# Rev1_7.net
KiCad netlist of a schematic drawn in EAGLE
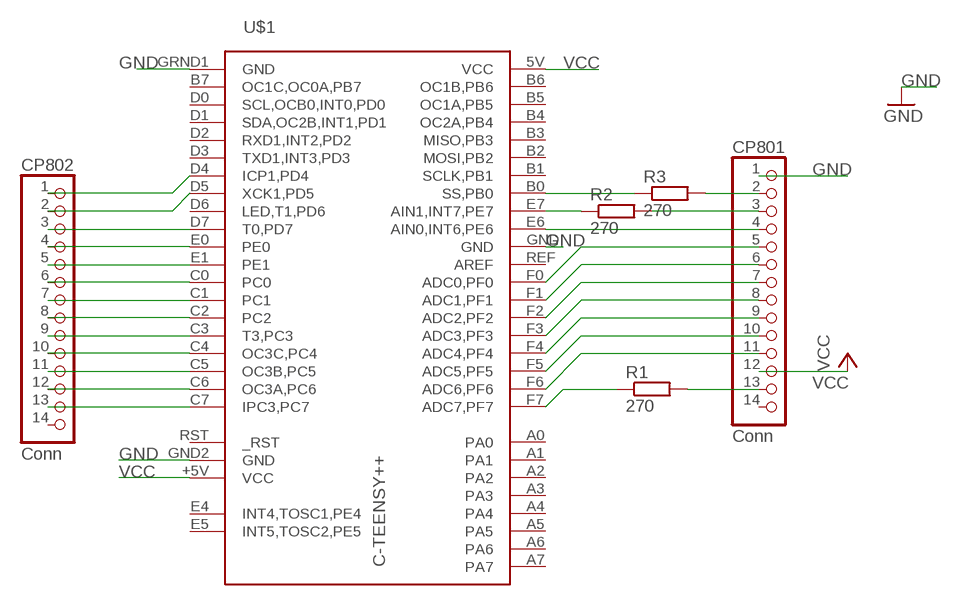
[diagram p0: schematic, sheet 1]

(export (version "E")
  (design (tool "Eeschema 10.0.6"))
  (components
    (comp (ref "CP801")
      (value "Conn")
      (footprint "eagle-import:1X14")
      (libsource (lib "eagle-import") (part "PINHD-1X14"))
    )
    (comp (ref "CP802")
      (value "Conn")
      (footprint "eagle-import:1X14")
      (libsource (lib "eagle-import") (part "PINHD-1X14"))
    )
    (comp (ref "R1")
      (value "270")
      (footprint "eagle-import:R0805")
      (libsource (lib "eagle-import") (part "R-EU_R0805"))
    )
    (comp (ref "R2")
      (value "270")
      (footprint "eagle-import:R0805")
      (libsource (lib "eagle-import") (part "R-EU_R0805"))
    )
    (comp (ref "R3")
      (value "270")
      (footprint "eagle-import:R0805")
      (libsource (lib "eagle-import") (part "R-EU_R0805"))
    )
    (comp (ref "U$1")
      (value "C-TEENSY++")
      (footprint "eagle-import:TEENSY++")
      (libsource (lib "eagle-import") (part "C-TEENSY++"))
    )
  )
  (nets
    (net (code "1") (name "GND") (class "Default")
      (node (ref "CP801") (pin "1") (pinfunction "1_1") (pintype "passive"))
      (node (ref "U$1") (pin "GND") (pinfunction "GND_GND") (pintype "power_in"))
      (node (ref "U$1") (pin "GND2") (pinfunction "GND_GND2") (pintype "power_in"))
      (node (ref "U$1") (pin "GRND1") (pinfunction "GND_GRND1") (pintype "power_in"))
    )
    (net (code "2") (name "Net-(CP801-Pad2)") (class "Default")
      (node (ref "CP801") (pin "2") (pinfunction "2_2") (pintype "passive"))
      (node (ref "R3") (pin "2") (pinfunction "2_2") (pintype "passive"))
    )
    (net (code "3") (name "Net-(CP801-Pad3)") (class "Default")
      (node (ref "CP801") (pin "3") (pinfunction "3_3") (pintype "passive"))
      (node (ref "R2") (pin "2") (pinfunction "2_2") (pintype "passive"))
    )
    (net (code "4") (name "Net-(CP801-Pad13)") (class "Default")
      (node (ref "CP801") (pin "13") (pinfunction "13_13") (pintype "passive"))
      (node (ref "R1") (pin "2") (pinfunction "2_2") (pintype "passive"))
    )
    (net (code "5") (name "Net-(U$1-ADC0,PF0)") (class "Default")
      (node (ref "CP801") (pin "5") (pinfunction "5_5") (pintype "passive"))
      (node (ref "U$1") (pin "F0") (pinfunction "ADC0,PF0_F0") (pintype "bidirectional"))
    )
    (net (code "6") (name "Net-(U$1-ADC1,PF1)") (class "Default")
      (node (ref "CP801") (pin "6") (pinfunction "6_6") (pintype "passive"))
      (node (ref "U$1") (pin "F1") (pinfunction "ADC1,PF1_F1") (pintype "bidirectional"))
    )
    (net (code "7") (name "Net-(U$1-ADC2,PF2)") (class "Default")
      (node (ref "CP801") (pin "7") (pinfunction "7_7") (pintype "passive"))
      (node (ref "U$1") (pin "F2") (pinfunction "ADC2,PF2_F2") (pintype "bidirectional"))
    )
    (net (code "8") (name "Net-(U$1-ADC3,PF3)") (class "Default")
      (node (ref "CP801") (pin "8") (pinfunction "8_8") (pintype "passive"))
      (node (ref "U$1") (pin "F3") (pinfunction "ADC3,PF3_F3") (pintype "bidirectional"))
    )
    (net (code "9") (name "Net-(U$1-ADC4,PF4)") (class "Default")
      (node (ref "CP801") (pin "9") (pinfunction "9_9") (pintype "passive"))
      (node (ref "U$1") (pin "F4") (pinfunction "ADC4,PF4_F4") (pintype "bidirectional"))
    )
    (net (code "10") (name "Net-(U$1-ADC5,PF5)") (class "Default")
      (node (ref "CP801") (pin "10") (pinfunction "10_10") (pintype "passive"))
      (node (ref "U$1") (pin "F5") (pinfunction "ADC5,PF5_F5") (pintype "bidirectional"))
    )
    (net (code "11") (name "Net-(U$1-ADC6,PF6)") (class "Default")
      (node (ref "CP801") (pin "11") (pinfunction "11_11") (pintype "passive"))
      (node (ref "U$1") (pin "F6") (pinfunction "ADC6,PF6_F6") (pintype "bidirectional"))
    )
    (net (code "12") (name "Net-(U$1-ADC7,PF7)") (class "Default")
      (node (ref "R1") (pin "1") (pinfunction "1_1") (pintype "passive"))
      (node (ref "U$1") (pin "F7") (pinfunction "ADC7,PF7_F7") (pintype "bidirectional"))
    )
    (net (code "13") (name "Net-(U$1-AIN0,INT6,PE6)") (class "Default")
      (node (ref "CP801") (pin "4") (pinfunction "4_4") (pintype "passive"))
      (node (ref "U$1") (pin "E6") (pinfunction "AIN0,INT6,PE6_E6") (pintype "bidirectional"))
    )
    (net (code "14") (name "Net-(U$1-AIN1,INT7,PE7)") (class "Default")
      (node (ref "R2") (pin "1") (pinfunction "1_1") (pintype "passive"))
      (node (ref "U$1") (pin "E7") (pinfunction "AIN1,INT7,PE7_E7") (pintype "bidirectional"))
    )
    (net (code "15") (name "Net-(U$1-ICP1,PD4)") (class "Default")
      (node (ref "CP802") (pin "1") (pinfunction "1_1") (pintype "passive"))
      (node (ref "U$1") (pin "D4") (pinfunction "ICP1,PD4_D4") (pintype "bidirectional"))
    )
    (net (code "16") (name "Net-(U$1-IPC3,PC7)") (class "Default")
      (node (ref "CP802") (pin "13") (pinfunction "13_13") (pintype "passive"))
      (node (ref "U$1") (pin "C7") (pinfunction "IPC3,PC7_C7") (pintype "bidirectional"))
    )
    (net (code "17") (name "Net-(U$1-OC3A,PC6)") (class "Default")
      (node (ref "CP802") (pin "12") (pinfunction "12_12") (pintype "passive"))
      (node (ref "U$1") (pin "C6") (pinfunction "OC3A,PC6_C6") (pintype "bidirectional"))
    )
    (net (code "18") (name "Net-(U$1-OC3B,PC5)") (class "Default")
      (node (ref "CP802") (pin "11") (pinfunction "11_11") (pintype "passive"))
      (node (ref "U$1") (pin "C5") (pinfunction "OC3B,PC5_C5") (pintype "bidirectional"))
    )
    (net (code "19") (name "Net-(U$1-OC3C,PC4)") (class "Default")
      (node (ref "CP802") (pin "10") (pinfunction "10_10") (pintype "passive"))
      (node (ref "U$1") (pin "C4") (pinfunction "OC3C,PC4_C4") (pintype "bidirectional"))
    )
    (net (code "20") (name "Net-(U$1-PC0)") (class "Default")
      (node (ref "CP802") (pin "6") (pinfunction "6_6") (pintype "passive"))
      (node (ref "U$1") (pin "C0") (pinfunction "PC0_C0") (pintype "bidirectional"))
    )
    (net (code "21") (name "Net-(U$1-PC1)") (class "Default")
      (node (ref "CP802") (pin "7") (pinfunction "7_7") (pintype "passive"))
      (node (ref "U$1") (pin "C1") (pinfunction "PC1_C1") (pintype "bidirectional"))
    )
    (net (code "22") (name "Net-(U$1-PC2)") (class "Default")
      (node (ref "CP802") (pin "8") (pinfunction "8_8") (pintype "passive"))
      (node (ref "U$1") (pin "C2") (pinfunction "PC2_C2") (pintype "bidirectional"))
    )
    (net (code "23") (name "Net-(U$1-PE0)") (class "Default")
      (node (ref "CP802") (pin "4") (pinfunction "4_4") (pintype "passive"))
      (node (ref "U$1") (pin "E0") (pinfunction "PE0_E0") (pintype "bidirectional"))
    )
    (net (code "24") (name "Net-(U$1-PE1)") (class "Default")
      (node (ref "CP802") (pin "5") (pinfunction "5_5") (pintype "passive"))
      (node (ref "U$1") (pin "E1") (pinfunction "PE1_E1") (pintype "bidirectional"))
    )
    (net (code "25") (name "Net-(U$1-SS,PB0)") (class "Default")
      (node (ref "R3") (pin "1") (pinfunction "1_1") (pintype "passive"))
      (node (ref "U$1") (pin "B0") (pinfunction "SS,PB0_B0") (pintype "bidirectional"))
    )
    (net (code "26") (name "Net-(U$1-T0,PD7)") (class "Default")
      (node (ref "CP802") (pin "3") (pinfunction "3_3") (pintype "passive"))
      (node (ref "U$1") (pin "D7") (pinfunction "T0,PD7_D7") (pintype "bidirectional"))
    )
    (net (code "27") (name "Net-(U$1-T3,PC3)") (class "Default")
      (node (ref "CP802") (pin "9") (pinfunction "9_9") (pintype "passive"))
      (node (ref "U$1") (pin "C3") (pinfunction "T3,PC3_C3") (pintype "bidirectional"))
    )
    (net (code "28") (name "Net-(U$1-XCK1,PD5)") (class "Default")
      (node (ref "CP802") (pin "2") (pinfunction "2_2") (pintype "passive"))
      (node (ref "U$1") (pin "D5") (pinfunction "XCK1,PD5_D5") (pintype "bidirectional"))
    )
    (net (code "29") (name "VCC") (class "Default")
      (node (ref "CP801") (pin "12") (pinfunction "12_12") (pintype "passive"))
      (node (ref "U$1") (pin "+5V") (pinfunction "VCC_+5V") (pintype "power_in"))
      (node (ref "U$1") (pin "5V") (pinfunction "VCC_5V") (pintype "power_in"))
    )
    (net (code "30") (name "unconnected-(CP801-Pad14)") (class "Default")
      (node (ref "CP801") (pin "14") (pinfunction "14_14") (pintype "passive"))
    )
    (net (code "31") (name "unconnected-(CP802-Pad14)") (class "Default")
      (node (ref "CP802") (pin "14") (pinfunction "14_14") (pintype "passive"))
    )
    (net (code "32") (name "unconnected-(U$1-AREF-PadREF)") (class "Default")
      (node (ref "U$1") (pin "REF") (pinfunction "AREF_REF") (pintype "input"))
    )
    (net (code "33") (name "unconnected-(U$1-INT4,TOSC1,PE4-PadE4)") (class "Default")
      (node (ref "U$1") (pin "E4") (pinfunction "INT4,TOSC1,PE4_E4") (pintype "bidirectional"))
    )
    (net (code "34") (name "unconnected-(U$1-INT5,TOSC2,PE5-PadE5)") (class "Default")
      (node (ref "U$1") (pin "E5") (pinfunction "INT5,TOSC2,PE5_E5") (pintype "bidirectional"))
    )
    (net (code "35") (name "unconnected-(U$1-LED,T1,PD6-PadD6)") (class "Default")
      (node (ref "U$1") (pin "D6") (pinfunction "LED,T1,PD6_D6") (pintype "bidirectional"))
    )
    (net (code "36") (name "unconnected-(U$1-MISO,PB3-PadB3)") (class "Default")
      (node (ref "U$1") (pin "B3") (pinfunction "MISO,PB3_B3") (pintype "bidirectional"))
    )
    (net (code "37") (name "unconnected-(U$1-MOSI,PB2-PadB2)") (class "Default")
      (node (ref "U$1") (pin "B2") (pinfunction "MOSI,PB2_B2") (pintype "bidirectional"))
    )
    (net (code "38") (name "unconnected-(U$1-OC1A,PB5-PadB5)") (class "Default")
      (node (ref "U$1") (pin "B5") (pinfunction "OC1A,PB5_B5") (pintype "bidirectional"))
    )
    (net (code "39") (name "unconnected-(U$1-OC1B,PB6-PadB6)") (class "Default")
      (node (ref "U$1") (pin "B6") (pinfunction "OC1B,PB6_B6") (pintype "bidirectional"))
    )
    (net (code "40") (name "unconnected-(U$1-OC1C,OC0A,PB7-PadB7)") (class "Default")
      (node (ref "U$1") (pin "B7") (pinfunction "OC1C,OC0A,PB7_B7") (pintype "bidirectional"))
    )
    (net (code "41") (name "unconnected-(U$1-OC2A,PB4-PadB4)") (class "Default")
      (node (ref "U$1") (pin "B4") (pinfunction "OC2A,PB4_B4") (pintype "bidirectional"))
    )
    (net (code "42") (name "unconnected-(U$1-PA0-PadA0)") (class "Default")
      (node (ref "U$1") (pin "A0") (pinfunction "PA0_A0") (pintype "bidirectional"))
    )
    (net (code "43") (name "unconnected-(U$1-PA1-PadA1)") (class "Default")
      (node (ref "U$1") (pin "A1") (pinfunction "PA1_A1") (pintype "bidirectional"))
    )
    (net (code "44") (name "unconnected-(U$1-PA2-PadA2)") (class "Default")
      (node (ref "U$1") (pin "A2") (pinfunction "PA2_A2") (pintype "bidirectional"))
    )
    (net (code "45") (name "unconnected-(U$1-PA3-PadA3)") (class "Default")
      (node (ref "U$1") (pin "A3") (pinfunction "PA3_A3") (pintype "bidirectional"))
    )
    (net (code "46") (name "unconnected-(U$1-PA4-PadA4)") (class "Default")
      (node (ref "U$1") (pin "A4") (pinfunction "PA4_A4") (pintype "bidirectional"))
    )
    (net (code "47") (name "unconnected-(U$1-PA5-PadA5)") (class "Default")
      (node (ref "U$1") (pin "A5") (pinfunction "PA5_A5") (pintype "bidirectional"))
    )
    (net (code "48") (name "unconnected-(U$1-PA6-PadA6)") (class "Default")
      (node (ref "U$1") (pin "A6") (pinfunction "PA6_A6") (pintype "bidirectional"))
    )
    (net (code "49") (name "unconnected-(U$1-PA7-PadA7)") (class "Default")
      (node (ref "U$1") (pin "A7") (pinfunction "PA7_A7") (pintype "bidirectional"))
    )
    (net (code "50") (name "unconnected-(U$1-RXD1,INT2,PD2-PadD2)") (class "Default")
      (node (ref "U$1") (pin "D2") (pinfunction "RXD1,INT2,PD2_D2") (pintype "bidirectional"))
    )
    (net (code "51") (name "unconnected-(U$1-SCL,OCB0,INT0,PD0-PadD0)") (class "Default")
      (node (ref "U$1") (pin "D0") (pinfunction "SCL,OCB0,INT0,PD0_D0") (pintype "bidirectional"))
    )
    (net (code "52") (name "unconnected-(U$1-SCLK,PB1-PadB1)") (class "Default")
      (node (ref "U$1") (pin "B1") (pinfunction "SCLK,PB1_B1") (pintype "bidirectional"))
    )
    (net (code "53") (name "unconnected-(U$1-SDA,OC2B,INT1,PD1-PadD1)") (class "Default")
      (node (ref "U$1") (pin "D1") (pinfunction "SDA,OC2B,INT1,PD1_D1") (pintype "bidirectional"))
    )
    (net (code "54") (name "unconnected-(U$1-TXD1,INT3,PD3-PadD3)") (class "Default")
      (node (ref "U$1") (pin "D3") (pinfunction "TXD1,INT3,PD3_D3") (pintype "bidirectional"))
    )
    (net (code "55") (name "unconnected-(U$1-_RST-PadRST)") (class "Default")
      (node (ref "U$1") (pin "RST") (pinfunction "_RST_RST") (pintype "input"))
    )
  )
)
